# XBee.net
KiCad netlist of a schematic drawn in Altium Designer
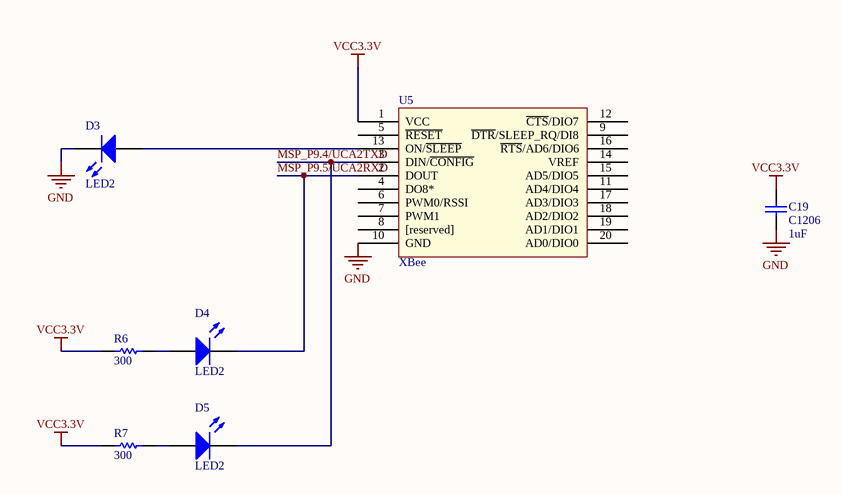
[diagram p0: XBee.SchDoc]

(export (version "E")
  (design (tool "Eeschema 10.0.6"))
  (components
    (comp (ref "C19")
      (value "C1206")
      (footprint "1206")
      (description "Ceramic Chip Capacitor - Standard")
      (fields (field (name "ALTIUM_VALUE") "1uF") (field (name "PUBLISHER") "Altium Limited"))
      (libsource (lib "KEMET Chip Capacitor") (part "C1206"))
    )
    (comp (ref "D3")
      (value "LED2")
      (footprint "DSO-F2/D6.1")
      (description "Typical RED, GREEN, YELLOW, AMBER GaAs LED")
      (fields (field (name "PUBLISHER") "Altium Limited"))
      (libsource (lib "Miscellaneous Devices") (part "LED2"))
    )
    (comp (ref "D4")
      (value "LED2")
      (footprint "DSO-F2/D6.1")
      (description "Typical RED, GREEN, YELLOW, AMBER GaAs LED")
      (fields (field (name "PUBLISHER") "Altium Limited"))
      (libsource (lib "Miscellaneous Devices") (part "LED2"))
    )
    (comp (ref "D5")
      (value "LED2")
      (footprint "DSO-F2/D6.1")
      (description "Typical RED, GREEN, YELLOW, AMBER GaAs LED")
      (fields (field (name "PUBLISHER") "Altium Limited"))
      (libsource (lib "Miscellaneous Devices") (part "LED2"))
    )
    (comp (ref "R6")
      (value "300")
      (footprint "8-1206")
      (description "Thick Film Chip Resistor, 1 Ohm to 10M Ohm Range, 5% Tolerance, 1206 Size, 0.25 W")
      (fields (field (name "PUBLISHER") "Altium Limited"))
      (libsource (lib "Panasonic Resistor") (part "ERJ8GE"))
    )
    (comp (ref "R7")
      (value "300")
      (footprint "8-1206")
      (description "Thick Film Chip Resistor, 1 Ohm to 10M Ohm Range, 5% Tolerance, 1206 Size, 0.25 W")
      (fields (field (name "PUBLISHER") "Altium Limited"))
      (libsource (lib "Panasonic Resistor") (part "ERJ8GE"))
    )
    (comp (ref "U5") (value "XBee") (footprint "XBee:PCBComponent_1") (libsource (lib "XBee") (part "XBee")))
  )
  (nets
    (net (code "1") (name "/MSP_P9.4{slash}UCA2TXD") (class "Default")
      (node (ref "D5") (pin "2") (pinfunction "K_2") (pintype "passive"))
      (node (ref "U5") (pin "3") (pinfunction "DIN/~{CONFIG}_3") (pintype "passive"))
    )
    (net (code "2") (name "/MSP_P9.5{slash}UCA2RXD") (class "Default")
      (node (ref "D4") (pin "2") (pinfunction "K_2") (pintype "passive"))
      (node (ref "U5") (pin "2") (pinfunction "DOUT_2") (pintype "passive"))
    )
    (net (code "3") (name "GND") (class "Default")
      (node (ref "C19") (pin "1") (pinfunction "1_1") (pintype "passive"))
      (node (ref "D3") (pin "2") (pinfunction "K_2") (pintype "passive"))
      (node (ref "U5") (pin "10") (pinfunction "GND_10") (pintype "passive"))
    )
    (net (code "4") (name "Net-(D3-A)") (class "Default")
      (node (ref "D3") (pin "1") (pinfunction "A_1") (pintype "passive"))
      (node (ref "U5") (pin "13") (pinfunction "ON/~{SLEEP}_13") (pintype "passive"))
    )
    (net (code "5") (name "Net-(D4-A)") (class "Default")
      (node (ref "D4") (pin "1") (pinfunction "A_1") (pintype "passive"))
      (node (ref "R6") (pin "2") (pinfunction "2_2") (pintype "passive"))
    )
    (net (code "6") (name "Net-(D5-A)") (class "Default")
      (node (ref "D5") (pin "1") (pinfunction "A_1") (pintype "passive"))
      (node (ref "R7") (pin "2") (pinfunction "2_2") (pintype "passive"))
    )
    (net (code "7") (name "VCC3.3V") (class "Default")
      (node (ref "C19") (pin "2") (pinfunction "2_2") (pintype "passive"))
      (node (ref "R6") (pin "1") (pinfunction "1_1") (pintype "passive"))
      (node (ref "R7") (pin "1") (pinfunction "1_1") (pintype "passive"))
      (node (ref "U5") (pin "1") (pinfunction "VCC_1") (pintype "passive"))
    )
    (net (code "8") (name "unconnected-(U5-AD0{slash}DIO0-Pad20)") (class "Default")
      (node (ref "U5") (pin "20") (pinfunction "AD0/DIO0_20") (pintype "passive"))
    )
    (net (code "9") (name "unconnected-(U5-AD1{slash}DIO1-Pad19)") (class "Default")
      (node (ref "U5") (pin "19") (pinfunction "AD1/DIO1_19") (pintype "passive"))
    )
    (net (code "10") (name "unconnected-(U5-AD2{slash}DIO2-Pad18)") (class "Default")
      (node (ref "U5") (pin "18") (pinfunction "AD2/DIO2_18") (pintype "passive"))
    )
    (net (code "11") (name "unconnected-(U5-AD3{slash}DIO3-Pad17)") (class "Default")
      (node (ref "U5") (pin "17") (pinfunction "AD3/DIO3_17") (pintype "passive"))
    )
    (net (code "12") (name "unconnected-(U5-AD4{slash}DIO4-Pad11)") (class "Default")
      (node (ref "U5") (pin "11") (pinfunction "AD4/DIO4_11") (pintype "passive"))
    )
    (net (code "13") (name "unconnected-(U5-AD5{slash}DIO5-Pad15)") (class "Default")
      (node (ref "U5") (pin "15") (pinfunction "AD5/DIO5_15") (pintype "passive"))
    )
    (net (code "14") (name "unconnected-(U5-DO8*-Pad4)") (class "Default")
      (node (ref "U5") (pin "4") (pinfunction "DO8*_4") (pintype "passive"))
    )
    (net (code "15") (name "unconnected-(U5-PWM0{slash}RSSI-Pad6)") (class "Default")
      (node (ref "U5") (pin "6") (pinfunction "PWM0/RSSI_6") (pintype "passive"))
    )
    (net (code "16") (name "unconnected-(U5-PWM1-Pad7)") (class "Default")
      (node (ref "U5") (pin "7") (pinfunction "PWM1_7") (pintype "passive"))
    )
    (net (code "17") (name "unconnected-(U5-VREF-Pad14)") (class "Default")
      (node (ref "U5") (pin "14") (pinfunction "VREF_14") (pintype "passive"))
    )
    (net (code "18") (name "unconnected-(U5-[reserved]-Pad8)") (class "Default")
      (node (ref "U5") (pin "8") (pinfunction "[reserved]_8") (pintype "passive"))
    )
    (net (code "19") (name "unconnected-(U5-~{CTS}{slash}DIO7-Pad12)") (class "Default")
      (node (ref "U5") (pin "12") (pinfunction "~{CTS}/DIO7_12") (pintype "passive"))
    )
    (net (code "20") (name "unconnected-(U5-~{DTR}{slash}SLEEP_RQ{slash}DI8-Pad9)") (class "Default")
      (node (ref "U5") (pin "9") (pinfunction "~{DTR}/SLEEP_RQ/DI8_9") (pintype "passive"))
    )
    (net (code "21") (name "unconnected-(U5-~{RESET}-Pad5)") (class "Default")
      (node (ref "U5") (pin "5") (pinfunction "~{RESET}_5") (pintype "passive"))
    )
    (net (code "22") (name "unconnected-(U5-~{RTS}{slash}AD6{slash}DIO6-Pad16)") (class "Default")
      (node (ref "U5") (pin "16") (pinfunction "~{RTS}/AD6/DIO6_16") (pintype "passive"))
    )
  )
)
